# elric20-01B.net
KiCad netlist of a schematic drawn in EAGLE
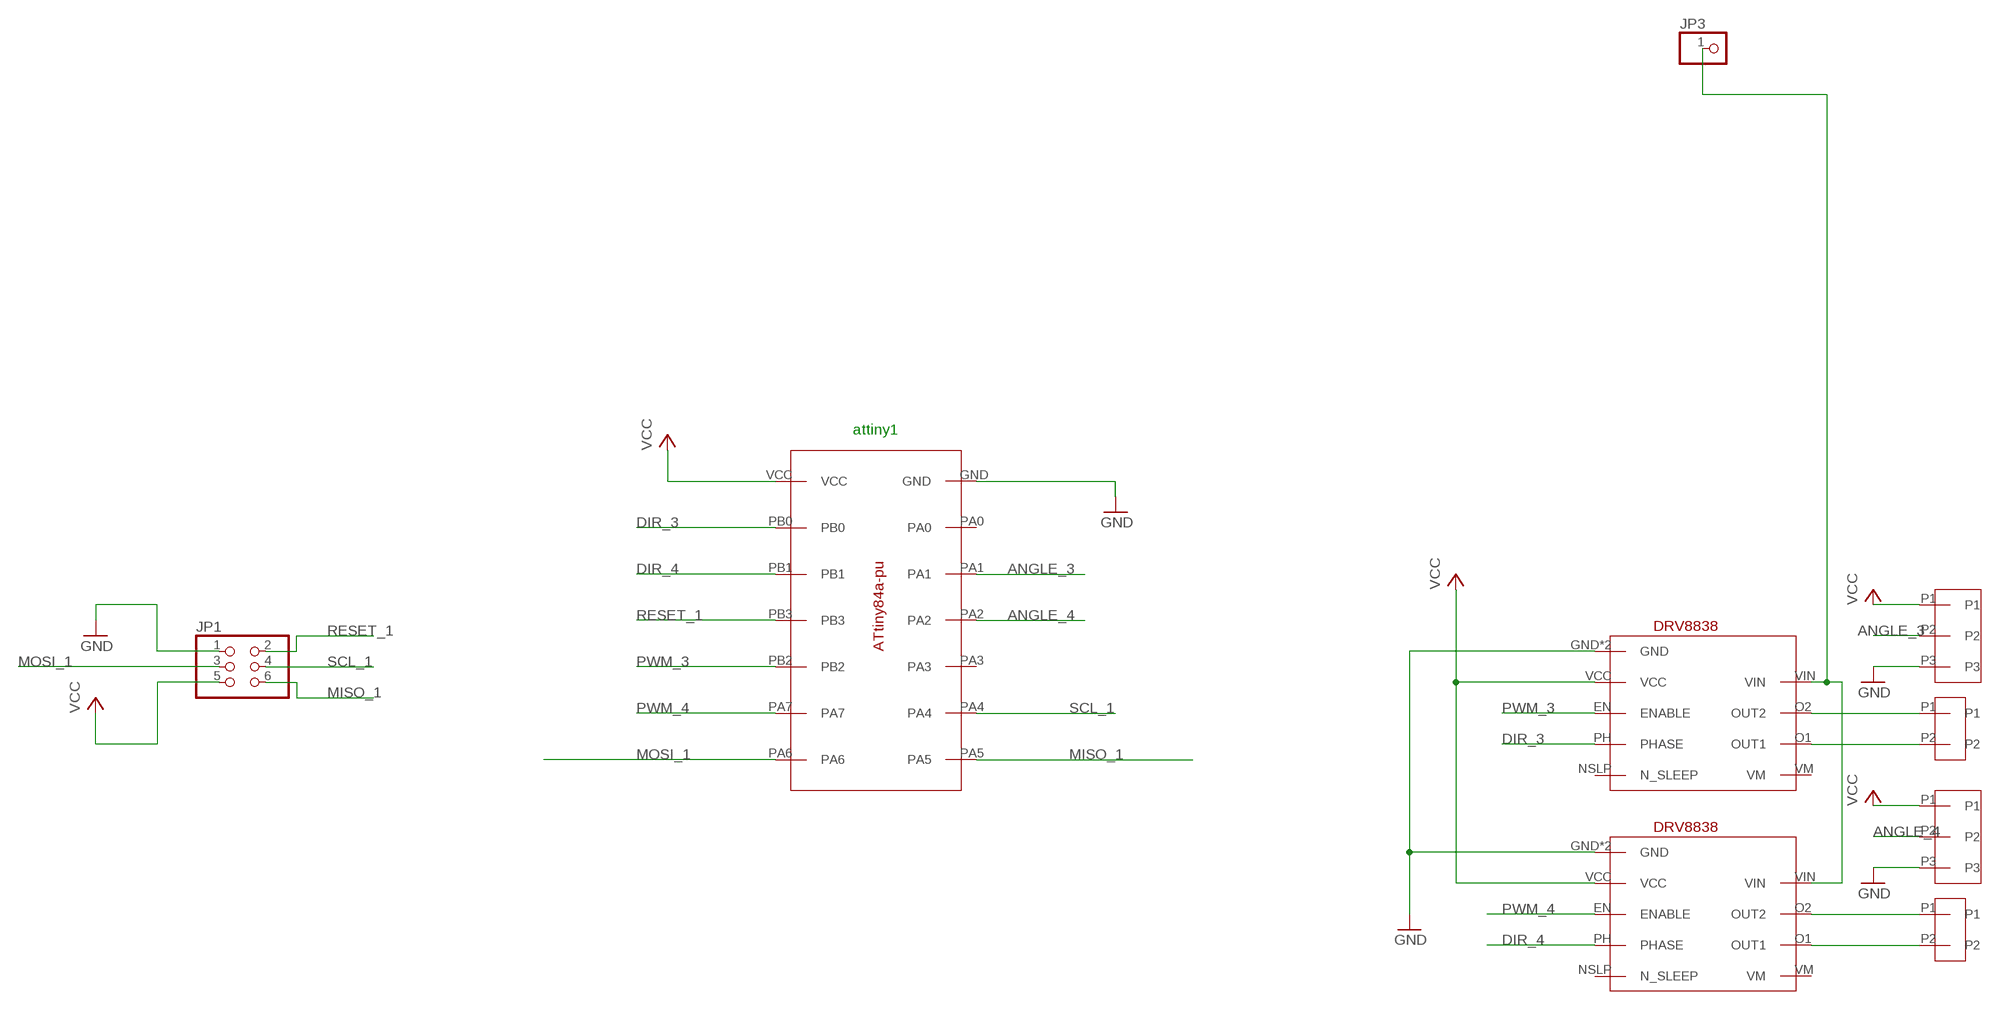
[diagram p0: schematic, sheet 1]

(export (version "E")
  (design (tool "Eeschema 10.0.6"))
  (components
    (comp (ref "JP1")
      (value "PINHD-2X3")
      (footprint "eagle-import:2X03")
      (libsource (lib "eagle-import") (part "PINHD-2X3"))
    )
    (comp (ref "JP3")
      (value "PINHD-1X1")
      (footprint "eagle-import:1X01")
      (libsource (lib "eagle-import") (part "PINHD-1X1"))
    )
    (comp (ref "U$4")
      (value "DRV8838")
      (footprint "eagle-import:DRV8838")
      (libsource (lib "eagle-import") (part "DRV8838"))
    )
    (comp (ref "U$5")
      (value "DRV8838")
      (footprint "eagle-import:DRV8838")
      (libsource (lib "eagle-import") (part "DRV8838"))
    )
    (comp (ref "U$8")
      (value "ATTINY84A-PU")
      (footprint "eagle-import:ATTINY84A-PU")
      (libsource (lib "eagle-import") (part "ATTINY84A-PU"))
    )
    (comp (ref "U$11")
      (value "PAD_SMD_X2_BIG")
      (footprint "eagle-import:PAD_SMD_X2_BIG")
      (libsource (lib "eagle-import") (part "PAD_SMD_X2_BIG"))
    )
    (comp (ref "U$12")
      (value "PAD_SMD_X2_BIG")
      (footprint "eagle-import:PAD_SMD_X2_BIG")
      (libsource (lib "eagle-import") (part "PAD_SMD_X2_BIG"))
    )
    (comp (ref "U$17")
      (value "PAD_SMD_X3")
      (footprint "eagle-import:PAD_SMD_X3")
      (libsource (lib "eagle-import") (part "PAD_SMD_X3"))
    )
    (comp (ref "U$18")
      (value "PAD_SMD_X3")
      (footprint "eagle-import:PAD_SMD_X3")
      (libsource (lib "eagle-import") (part "PAD_SMD_X3"))
    )
  )
  (nets
    (net (code "1") (name "/ANGLE_3") (class "Default")
      (node (ref "U$18") (pin "P2") (pinfunction "P2_P2") (pintype "bidirectional"))
      (node (ref "U$8") (pin "PA1") (pinfunction "PA1_PA1") (pintype "bidirectional"))
    )
    (net (code "2") (name "/ANGLE_4") (class "Default")
      (node (ref "U$17") (pin "P2") (pinfunction "P2_P2") (pintype "bidirectional"))
      (node (ref "U$8") (pin "PA2") (pinfunction "PA2_PA2") (pintype "bidirectional"))
    )
    (net (code "3") (name "/DIR_3") (class "Default")
      (node (ref "U$4") (pin "PH") (pinfunction "PHASE_PH") (pintype "bidirectional"))
      (node (ref "U$8") (pin "PB0") (pinfunction "PB0_PB0") (pintype "bidirectional"))
    )
    (net (code "4") (name "/DIR_4") (class "Default")
      (node (ref "U$5") (pin "PH") (pinfunction "PHASE_PH") (pintype "bidirectional"))
      (node (ref "U$8") (pin "PB1") (pinfunction "PB1_PB1") (pintype "bidirectional"))
    )
    (net (code "5") (name "/MISO_1") (class "Default")
      (node (ref "JP1") (pin "6") (pinfunction "6_6") (pintype "passive"))
      (node (ref "U$8") (pin "PA5") (pinfunction "PA5_PA5") (pintype "bidirectional"))
    )
    (net (code "6") (name "/MOSI_1") (class "Default")
      (node (ref "JP1") (pin "3") (pinfunction "3_3") (pintype "passive"))
      (node (ref "U$8") (pin "PA6") (pinfunction "PA6_PA6") (pintype "bidirectional"))
    )
    (net (code "7") (name "/PWM_3") (class "Default")
      (node (ref "U$4") (pin "EN") (pinfunction "ENABLE_EN") (pintype "bidirectional"))
      (node (ref "U$8") (pin "PB2") (pinfunction "PB2_PB2") (pintype "bidirectional"))
    )
    (net (code "8") (name "/PWM_4") (class "Default")
      (node (ref "U$5") (pin "EN") (pinfunction "ENABLE_EN") (pintype "bidirectional"))
      (node (ref "U$8") (pin "PA7") (pinfunction "PA7_PA7") (pintype "bidirectional"))
    )
    (net (code "9") (name "/RESET_1") (class "Default")
      (node (ref "JP1") (pin "2") (pinfunction "2_2") (pintype "passive"))
      (node (ref "U$8") (pin "PB3") (pinfunction "PB3_PB3") (pintype "bidirectional"))
    )
    (net (code "10") (name "/SCL_1") (class "Default")
      (node (ref "JP1") (pin "4") (pinfunction "4_4") (pintype "passive"))
      (node (ref "U$8") (pin "PA4") (pinfunction "PA4_PA4") (pintype "bidirectional"))
    )
    (net (code "11") (name "GND") (class "Default")
      (node (ref "JP1") (pin "1") (pinfunction "1_1") (pintype "passive"))
      (node (ref "U$17") (pin "P3") (pinfunction "P3_P3") (pintype "bidirectional"))
      (node (ref "U$18") (pin "P3") (pinfunction "P3_P3") (pintype "bidirectional"))
      (node (ref "U$4") (pin "GND") (pinfunction "GND_GND") (pintype "bidirectional"))
      (node (ref "U$4") (pin "GND2") (pinfunction "GND_GND2") (pintype "bidirectional"))
      (node (ref "U$5") (pin "GND") (pinfunction "GND_GND") (pintype "bidirectional"))
      (node (ref "U$5") (pin "GND2") (pinfunction "GND_GND2") (pintype "bidirectional"))
      (node (ref "U$8") (pin "GND") (pinfunction "GND_GND") (pintype "bidirectional"))
    )
    (net (code "12") (name "Net-(JP3-Pad1)") (class "Default")
      (node (ref "JP3") (pin "1") (pinfunction "1_1") (pintype "passive"))
      (node (ref "U$4") (pin "VIN") (pinfunction "VIN_VIN") (pintype "bidirectional"))
      (node (ref "U$5") (pin "VIN") (pinfunction "VIN_VIN") (pintype "bidirectional"))
    )
    (net (code "13") (name "Net-(U$4-OUT1)") (class "Default")
      (node (ref "U$11") (pin "P2") (pinfunction "P2_P2") (pintype "bidirectional"))
      (node (ref "U$4") (pin "O1") (pinfunction "OUT1_O1") (pintype "bidirectional"))
    )
    (net (code "14") (name "Net-(U$4-OUT2)") (class "Default")
      (node (ref "U$11") (pin "P1") (pinfunction "P1_P1") (pintype "bidirectional"))
      (node (ref "U$4") (pin "O2") (pinfunction "OUT2_O2") (pintype "bidirectional"))
    )
    (net (code "15") (name "Net-(U$5-OUT1)") (class "Default")
      (node (ref "U$12") (pin "P2") (pinfunction "P2_P2") (pintype "bidirectional"))
      (node (ref "U$5") (pin "O1") (pinfunction "OUT1_O1") (pintype "bidirectional"))
    )
    (net (code "16") (name "Net-(U$5-OUT2)") (class "Default")
      (node (ref "U$12") (pin "P1") (pinfunction "P1_P1") (pintype "bidirectional"))
      (node (ref "U$5") (pin "O2") (pinfunction "OUT2_O2") (pintype "bidirectional"))
    )
    (net (code "17") (name "VCC") (class "Default")
      (node (ref "JP1") (pin "5") (pinfunction "5_5") (pintype "passive"))
      (node (ref "U$17") (pin "P1") (pinfunction "P1_P1") (pintype "bidirectional"))
      (node (ref "U$18") (pin "P1") (pinfunction "P1_P1") (pintype "bidirectional"))
      (node (ref "U$4") (pin "VCC") (pinfunction "VCC_VCC") (pintype "bidirectional"))
      (node (ref "U$5") (pin "VCC") (pinfunction "VCC_VCC") (pintype "bidirectional"))
      (node (ref "U$8") (pin "VCC") (pinfunction "VCC_VCC") (pintype "bidirectional"))
    )
    (net (code "18") (name "unconnected-(U$4-N_SLEEP-PadNSLP)") (class "Default")
      (node (ref "U$4") (pin "NSLP") (pinfunction "N_SLEEP_NSLP") (pintype "bidirectional"))
    )
    (net (code "19") (name "unconnected-(U$4-PadVM)") (class "Default")
      (node (ref "U$4") (pin "VM") (pinfunction "VM_VM") (pintype "bidirectional"))
    )
    (net (code "20") (name "unconnected-(U$5-N_SLEEP-PadNSLP)") (class "Default")
      (node (ref "U$5") (pin "NSLP") (pinfunction "N_SLEEP_NSLP") (pintype "bidirectional"))
    )
    (net (code "21") (name "unconnected-(U$5-PadVM)") (class "Default")
      (node (ref "U$5") (pin "VM") (pinfunction "VM_VM") (pintype "bidirectional"))
    )
    (net (code "22") (name "unconnected-(U$8-PadPA0)") (class "Default")
      (node (ref "U$8") (pin "PA0") (pinfunction "PA0_PA0") (pintype "bidirectional"))
    )
    (net (code "23") (name "unconnected-(U$8-PadPA3)") (class "Default")
      (node (ref "U$8") (pin "PA3") (pinfunction "PA3_PA3") (pintype "bidirectional"))
    )
  )
)
